# PGTNXEN_pitch_out.net
KiCad netlist of a schematic drawn in EAGLE
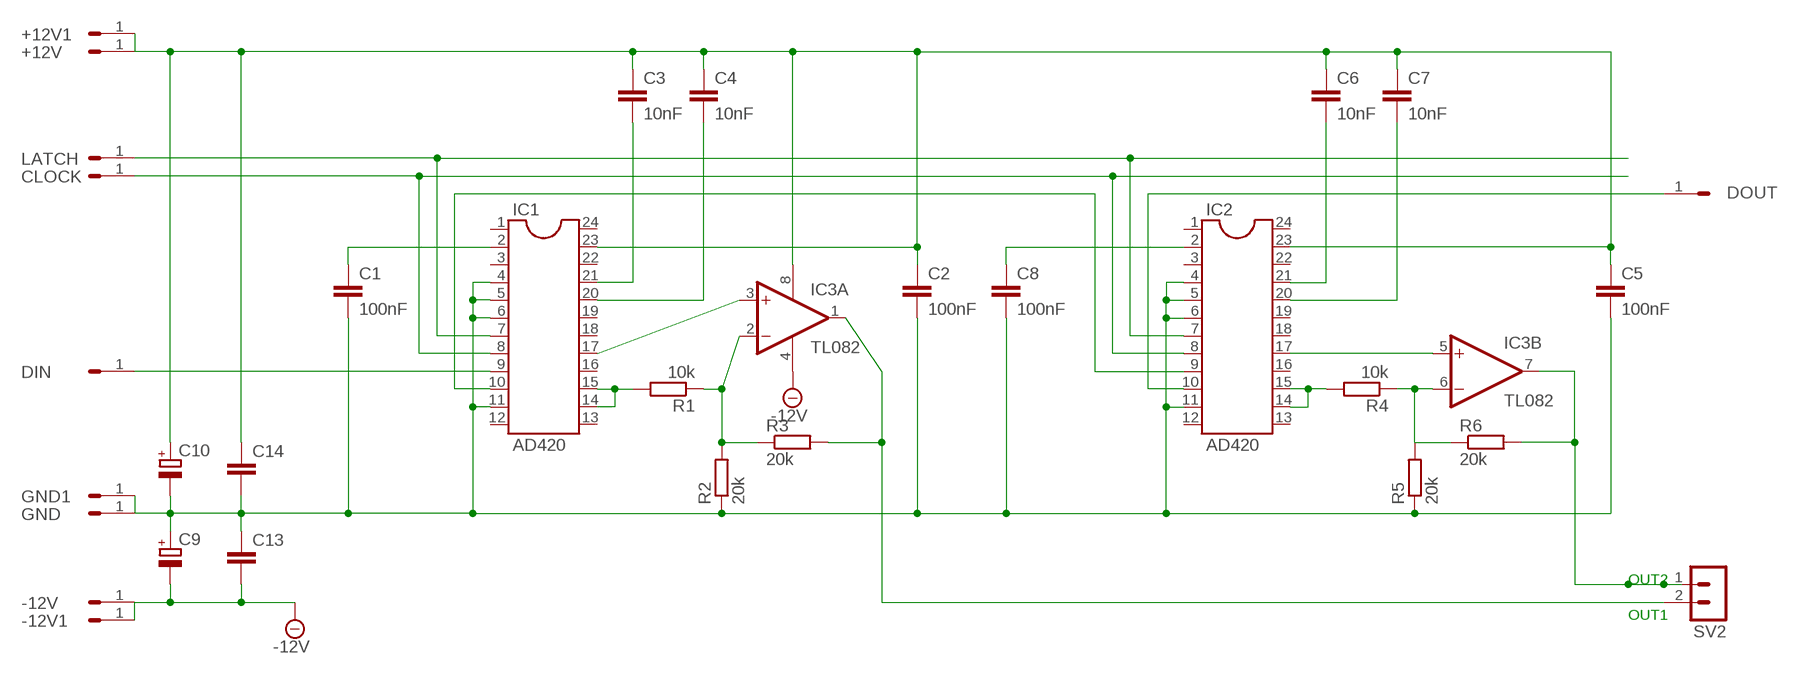
[diagram p0: schematic, sheet 1]

(export (version "E")
  (design (tool "Eeschema 10.0.6"))
  (components
    (comp (ref "+12V")
      (value "HEADER/MALE/01")
      (footprint "eagle-import:HEADER_MALE_01")
      (libsource (lib "eagle-import") (part "HEADER/MALE/01"))
    )
    (comp (ref "+12V1")
      (value "HEADER/MALE/01")
      (footprint "eagle-import:HEADER_MALE_01")
      (libsource (lib "eagle-import") (part "HEADER/MALE/01"))
    )
    (comp (ref "-12V")
      (value "HEADER/MALE/01")
      (footprint "eagle-import:HEADER_MALE_01")
      (libsource (lib "eagle-import") (part "HEADER/MALE/01"))
    )
    (comp (ref "-12V1")
      (value "HEADER/MALE/01")
      (footprint "eagle-import:HEADER_MALE_01")
      (libsource (lib "eagle-import") (part "HEADER/MALE/01"))
    )
    (comp (ref "C1")
      (value "100nF")
      (footprint "eagle-import:CERAMICDISC_5")
      (libsource (lib "eagle-import") (part "CAPACITORCERAMICDISC/5"))
    )
    (comp (ref "C2")
      (value "100nF")
      (footprint "eagle-import:CERAMICDISC_5")
      (libsource (lib "eagle-import") (part "CAPACITORCERAMICDISC/5"))
    )
    (comp (ref "C3")
      (value "10nF")
      (footprint "eagle-import:CERAMICDISC_5")
      (libsource (lib "eagle-import") (part "CAPACITORCERAMICDISC/5"))
    )
    (comp (ref "C4")
      (value "10nF")
      (footprint "eagle-import:CERAMICDISC_5")
      (libsource (lib "eagle-import") (part "CAPACITORCERAMICDISC/5"))
    )
    (comp (ref "C5")
      (value "100nF")
      (footprint "eagle-import:CERAMICDISC_5")
      (libsource (lib "eagle-import") (part "CAPACITORCERAMICDISC/5"))
    )
    (comp (ref "C6")
      (value "10nF")
      (footprint "eagle-import:CERAMICDISC_5")
      (libsource (lib "eagle-import") (part "CAPACITORCERAMICDISC/5"))
    )
    (comp (ref "C7")
      (value "10nF")
      (footprint "eagle-import:CERAMICDISC_5")
      (libsource (lib "eagle-import") (part "CAPACITORCERAMICDISC/5"))
    )
    (comp (ref "C8")
      (value "100nF")
      (footprint "eagle-import:CERAMICDISC_5")
      (libsource (lib "eagle-import") (part "CAPACITORCERAMICDISC/5"))
    )
    (comp (ref "C9")
      (value "CAPACITOR/POLARIZEDE2.5-6")
      (footprint "eagle-import:E2,5-6")
      (libsource (lib "eagle-import") (part "CAPACITOR/POLARIZEDE2.5-6"))
    )
    (comp (ref "C10")
      (value "CAPACITOR/POLARIZEDE2.5-6")
      (footprint "eagle-import:E2,5-6")
      (libsource (lib "eagle-import") (part "CAPACITOR/POLARIZEDE2.5-6"))
    )
    (comp (ref "C13")
      (value "CAPACITORCERAMICDISC/5")
      (footprint "eagle-import:CERAMICDISC_5")
      (libsource (lib "eagle-import") (part "CAPACITORCERAMICDISC/5"))
    )
    (comp (ref "C14")
      (value "CAPACITORCERAMICDISC/5")
      (footprint "eagle-import:CERAMICDISC_5")
      (libsource (lib "eagle-import") (part "CAPACITORCERAMICDISC/5"))
    )
    (comp (ref "CLOCK")
      (value "HEADER/MALE/01")
      (footprint "eagle-import:HEADER_MALE_01")
      (libsource (lib "eagle-import") (part "HEADER/MALE/01"))
    )
    (comp (ref "DIN")
      (value "HEADER/MALE/01")
      (footprint "eagle-import:HEADER_MALE_01")
      (libsource (lib "eagle-import") (part "HEADER/MALE/01"))
    )
    (comp (ref "DOUT")
      (value "HEADER/MALE/01")
      (footprint "eagle-import:HEADER_MALE_01")
      (libsource (lib "eagle-import") (part "HEADER/MALE/01"))
    )
    (comp (ref "GND")
      (value "HEADER/MALE/01")
      (footprint "eagle-import:HEADER_MALE_01")
      (libsource (lib "eagle-import") (part "HEADER/MALE/01"))
    )
    (comp (ref "GND1")
      (value "HEADER/MALE/01")
      (footprint "eagle-import:HEADER_MALE_01")
      (libsource (lib "eagle-import") (part "HEADER/MALE/01"))
    )
    (comp (ref "IC1")
      (value "AD420")
      (footprint "eagle-import:DIL24-3")
      (libsource (lib "eagle-import") (part "DIL24-3"))
    )
    (comp (ref "IC2")
      (value "AD420")
      (footprint "eagle-import:DIL24-3")
      (libsource (lib "eagle-import") (part "DIL24-3"))
    )
    (comp (ref "IC3")
      (value "TL082")
      (footprint "eagle-import:DIL08")
      (libsource (lib "eagle-import") (part "LM358N"))
    )
    (comp (ref "LATCH")
      (value "HEADER/MALE/01")
      (footprint "eagle-import:HEADER_MALE_01")
      (libsource (lib "eagle-import") (part "HEADER/MALE/01"))
    )
    (comp (ref "R1")
      (value "10k")
      (footprint "eagle-import:0204_7")
      (libsource (lib "eagle-import") (part "R-EU_0204/7"))
    )
    (comp (ref "R2")
      (value "20k")
      (footprint "eagle-import:0204_7")
      (libsource (lib "eagle-import") (part "R-EU_0204/7"))
    )
    (comp (ref "R3")
      (value "20k")
      (footprint "eagle-import:RESISTOR_7.5")
      (libsource (lib "eagle-import") (part "RESISTORRESISTOR/UPRIGHT/7.5"))
    )
    (comp (ref "R4")
      (value "10k")
      (footprint "eagle-import:0204_7")
      (libsource (lib "eagle-import") (part "R-EU_0204/7"))
    )
    (comp (ref "R5")
      (value "20k")
      (footprint "eagle-import:0204_7")
      (libsource (lib "eagle-import") (part "R-EU_0204/7"))
    )
    (comp (ref "R6")
      (value "20k")
      (footprint "eagle-import:RESISTOR_7.5")
      (libsource (lib "eagle-import") (part "RESISTORRESISTOR/UPRIGHT/7.5"))
    )
    (comp (ref "SV2")
      (value "HEADER/MALE/02-1")
      (footprint "eagle-import:HEADER_MALE_02-1")
      (libsource (lib "eagle-import") (part "HEADER/MALE/02-1"))
    )
  )
  (nets
    (net (code "1") (name "-12V") (class "Default")
      (node (ref "-12V") (pin "1") (pinfunction "3_1") (pintype "passive"))
      (node (ref "-12V1") (pin "1") (pinfunction "3_1") (pintype "passive"))
      (node (ref "C13") (pin "2") (pinfunction "2_2") (pintype "passive"))
      (node (ref "C9") (pin "-") (pinfunction "-_-") (pintype "passive"))
      (node (ref "IC3") (pin "4") (pinfunction "V-_4") (pintype "power_in"))
    )
    (net (code "2") (name "Net-(+12V-3)") (class "Default")
      (node (ref "+12V") (pin "1") (pinfunction "3_1") (pintype "passive"))
      (node (ref "+12V1") (pin "1") (pinfunction "3_1") (pintype "passive"))
      (node (ref "C10") (pin "+") (pinfunction "+_+") (pintype "passive"))
      (node (ref "C14") (pin "1") (pinfunction "1_1") (pintype "passive"))
      (node (ref "C2") (pin "1") (pinfunction "1_1") (pintype "passive"))
      (node (ref "C3") (pin "1") (pinfunction "1_1") (pintype "passive"))
      (node (ref "C4") (pin "1") (pinfunction "1_1") (pintype "passive"))
      (node (ref "C5") (pin "1") (pinfunction "1_1") (pintype "passive"))
      (node (ref "C6") (pin "1") (pinfunction "1_1") (pintype "passive"))
      (node (ref "C7") (pin "1") (pinfunction "1_1") (pintype "passive"))
      (node (ref "IC1") (pin "23") (pinfunction "23_23") (pintype "passive"))
      (node (ref "IC2") (pin "23") (pinfunction "23_23") (pintype "passive"))
      (node (ref "IC3") (pin "8") (pinfunction "V+_8") (pintype "power_in"))
    )
    (net (code "3") (name "Net-(C1-Pad1)") (class "Default")
      (node (ref "C1") (pin "1") (pinfunction "1_1") (pintype "passive"))
      (node (ref "IC1") (pin "2") (pinfunction "2_2") (pintype "passive"))
    )
    (net (code "4") (name "Net-(C3-Pad2)") (class "Default")
      (node (ref "C3") (pin "2") (pinfunction "2_2") (pintype "passive"))
      (node (ref "IC1") (pin "21") (pinfunction "21_21") (pintype "passive"))
    )
    (net (code "5") (name "Net-(C4-Pad2)") (class "Default")
      (node (ref "C4") (pin "2") (pinfunction "2_2") (pintype "passive"))
      (node (ref "IC1") (pin "20") (pinfunction "20_20") (pintype "passive"))
    )
    (net (code "6") (name "Net-(C6-Pad2)") (class "Default")
      (node (ref "C6") (pin "2") (pinfunction "2_2") (pintype "passive"))
      (node (ref "IC2") (pin "21") (pinfunction "21_21") (pintype "passive"))
    )
    (net (code "7") (name "Net-(C7-Pad2)") (class "Default")
      (node (ref "C7") (pin "2") (pinfunction "2_2") (pintype "passive"))
      (node (ref "IC2") (pin "20") (pinfunction "20_20") (pintype "passive"))
    )
    (net (code "8") (name "Net-(C8-Pad1)") (class "Default")
      (node (ref "C8") (pin "1") (pinfunction "1_1") (pintype "passive"))
      (node (ref "IC2") (pin "2") (pinfunction "2_2") (pintype "passive"))
    )
    (net (code "9") (name "Net-(CLOCK-3)") (class "Default")
      (node (ref "CLOCK") (pin "1") (pinfunction "3_1") (pintype "passive"))
      (node (ref "IC1") (pin "8") (pinfunction "8_8") (pintype "passive"))
      (node (ref "IC2") (pin "8") (pinfunction "8_8") (pintype "passive"))
    )
    (net (code "10") (name "Net-(DIN-3)") (class "Default")
      (node (ref "DIN") (pin "1") (pinfunction "3_1") (pintype "passive"))
      (node (ref "IC1") (pin "9") (pinfunction "9_9") (pintype "passive"))
    )
    (net (code "11") (name "Net-(DOUT-3)") (class "Default")
      (node (ref "DOUT") (pin "1") (pinfunction "3_1") (pintype "passive"))
      (node (ref "IC2") (pin "10") (pinfunction "10_10") (pintype "passive"))
    )
    (net (code "12") (name "Net-(GND-3)") (class "Default")
      (node (ref "C1") (pin "2") (pinfunction "2_2") (pintype "passive"))
      (node (ref "C10") (pin "-") (pinfunction "-_-") (pintype "passive"))
      (node (ref "C13") (pin "1") (pinfunction "1_1") (pintype "passive"))
      (node (ref "C14") (pin "2") (pinfunction "2_2") (pintype "passive"))
      (node (ref "C2") (pin "2") (pinfunction "2_2") (pintype "passive"))
      (node (ref "C5") (pin "2") (pinfunction "2_2") (pintype "passive"))
      (node (ref "C8") (pin "2") (pinfunction "2_2") (pintype "passive"))
      (node (ref "C9") (pin "+") (pinfunction "+_+") (pintype "passive"))
      (node (ref "GND") (pin "1") (pinfunction "3_1") (pintype "passive"))
      (node (ref "GND1") (pin "1") (pinfunction "3_1") (pintype "passive"))
      (node (ref "IC1") (pin "11") (pinfunction "11_11") (pintype "passive"))
      (node (ref "IC1") (pin "4") (pinfunction "4_4") (pintype "passive"))
      (node (ref "IC1") (pin "5") (pinfunction "5_5") (pintype "passive"))
      (node (ref "IC1") (pin "6") (pinfunction "6_6") (pintype "passive"))
      (node (ref "IC2") (pin "11") (pinfunction "11_11") (pintype "passive"))
      (node (ref "IC2") (pin "4") (pinfunction "4_4") (pintype "passive"))
      (node (ref "IC2") (pin "5") (pinfunction "5_5") (pintype "passive"))
      (node (ref "IC2") (pin "6") (pinfunction "6_6") (pintype "passive"))
      (node (ref "R2") (pin "1") (pinfunction "1_1") (pintype "passive"))
      (node (ref "R5") (pin "1") (pinfunction "1_1") (pintype "passive"))
    )
    (net (code "13") (name "Net-(IC1-Pad10)") (class "Default")
      (node (ref "IC1") (pin "10") (pinfunction "10_10") (pintype "passive"))
      (node (ref "IC2") (pin "9") (pinfunction "9_9") (pintype "passive"))
    )
    (net (code "14") (name "Net-(IC1-Pad14)") (class "Default")
      (node (ref "IC1") (pin "14") (pinfunction "14_14") (pintype "passive"))
      (node (ref "IC1") (pin "15") (pinfunction "15_15") (pintype "passive"))
      (node (ref "R1") (pin "2") (pinfunction "2_2") (pintype "passive"))
    )
    (net (code "15") (name "Net-(IC2-Pad14)") (class "Default")
      (node (ref "IC2") (pin "14") (pinfunction "14_14") (pintype "passive"))
      (node (ref "IC2") (pin "15") (pinfunction "15_15") (pintype "passive"))
      (node (ref "R4") (pin "2") (pinfunction "2_2") (pintype "passive"))
    )
    (net (code "16") (name "Net-(IC3A-+IN)") (class "Default")
      (node (ref "IC1") (pin "17") (pinfunction "17_17") (pintype "passive"))
      (node (ref "IC3") (pin "3") (pinfunction "+IN_3") (pintype "input"))
    )
    (net (code "17") (name "Net-(IC3A--IN)") (class "Default")
      (node (ref "IC3") (pin "2") (pinfunction "-IN_2") (pintype "input"))
      (node (ref "R1") (pin "1") (pinfunction "1_1") (pintype "passive"))
      (node (ref "R2") (pin "2") (pinfunction "2_2") (pintype "passive"))
      (node (ref "R3") (pin "1") (pinfunction "1_1") (pintype "passive"))
    )
    (net (code "18") (name "Net-(IC3A-OUT)") (class "Default")
      (node (ref "IC3") (pin "1") (pinfunction "OUT_1") (pintype "output"))
      (node (ref "R3") (pin "2") (pinfunction "2_2") (pintype "passive"))
      (node (ref "SV2") (pin "2") (pinfunction "3_2") (pintype "passive"))
    )
    (net (code "19") (name "Net-(IC3B-+IN)") (class "Default")
      (node (ref "IC2") (pin "17") (pinfunction "17_17") (pintype "passive"))
      (node (ref "IC3") (pin "5") (pinfunction "+IN_5") (pintype "input"))
    )
    (net (code "20") (name "Net-(IC3B--IN)") (class "Default")
      (node (ref "IC3") (pin "6") (pinfunction "-IN_6") (pintype "input"))
      (node (ref "R4") (pin "1") (pinfunction "1_1") (pintype "passive"))
      (node (ref "R5") (pin "2") (pinfunction "2_2") (pintype "passive"))
      (node (ref "R6") (pin "1") (pinfunction "1_1") (pintype "passive"))
    )
    (net (code "21") (name "Net-(IC3B-OUT)") (class "Default")
      (node (ref "IC3") (pin "7") (pinfunction "OUT_7") (pintype "output"))
      (node (ref "R6") (pin "2") (pinfunction "2_2") (pintype "passive"))
      (node (ref "SV2") (pin "1") (pinfunction "2_1") (pintype "passive"))
    )
    (net (code "22") (name "Net-(LATCH-3)") (class "Default")
      (node (ref "IC1") (pin "7") (pinfunction "7_7") (pintype "passive"))
      (node (ref "IC2") (pin "7") (pinfunction "7_7") (pintype "passive"))
      (node (ref "LATCH") (pin "1") (pinfunction "3_1") (pintype "passive"))
    )
    (net (code "23") (name "unconnected-(IC1-Pad1)") (class "Default")
      (node (ref "IC1") (pin "1") (pinfunction "1_1") (pintype "passive"))
    )
    (net (code "24") (name "unconnected-(IC1-Pad3)") (class "Default")
      (node (ref "IC1") (pin "3") (pinfunction "3_3") (pintype "passive"))
    )
    (net (code "25") (name "unconnected-(IC1-Pad12)") (class "Default")
      (node (ref "IC1") (pin "12") (pinfunction "12_12") (pintype "passive"))
    )
    (net (code "26") (name "unconnected-(IC1-Pad13)") (class "Default")
      (node (ref "IC1") (pin "13") (pinfunction "13_13") (pintype "passive"))
    )
    (net (code "27") (name "unconnected-(IC1-Pad16)") (class "Default")
      (node (ref "IC1") (pin "16") (pinfunction "16_16") (pintype "passive"))
    )
    (net (code "28") (name "unconnected-(IC1-Pad18)") (class "Default")
      (node (ref "IC1") (pin "18") (pinfunction "18_18") (pintype "passive"))
    )
    (net (code "29") (name "unconnected-(IC1-Pad19)") (class "Default")
      (node (ref "IC1") (pin "19") (pinfunction "19_19") (pintype "passive"))
    )
    (net (code "30") (name "unconnected-(IC1-Pad22)") (class "Default")
      (node (ref "IC1") (pin "22") (pinfunction "22_22") (pintype "passive"))
    )
    (net (code "31") (name "unconnected-(IC1-Pad24)") (class "Default")
      (node (ref "IC1") (pin "24") (pinfunction "24_24") (pintype "passive"))
    )
    (net (code "32") (name "unconnected-(IC2-Pad1)") (class "Default")
      (node (ref "IC2") (pin "1") (pinfunction "1_1") (pintype "passive"))
    )
    (net (code "33") (name "unconnected-(IC2-Pad3)") (class "Default")
      (node (ref "IC2") (pin "3") (pinfunction "3_3") (pintype "passive"))
    )
    (net (code "34") (name "unconnected-(IC2-Pad12)") (class "Default")
      (node (ref "IC2") (pin "12") (pinfunction "12_12") (pintype "passive"))
    )
    (net (code "35") (name "unconnected-(IC2-Pad13)") (class "Default")
      (node (ref "IC2") (pin "13") (pinfunction "13_13") (pintype "passive"))
    )
    (net (code "36") (name "unconnected-(IC2-Pad16)") (class "Default")
      (node (ref "IC2") (pin "16") (pinfunction "16_16") (pintype "passive"))
    )
    (net (code "37") (name "unconnected-(IC2-Pad18)") (class "Default")
      (node (ref "IC2") (pin "18") (pinfunction "18_18") (pintype "passive"))
    )
    (net (code "38") (name "unconnected-(IC2-Pad19)") (class "Default")
      (node (ref "IC2") (pin "19") (pinfunction "19_19") (pintype "passive"))
    )
    (net (code "39") (name "unconnected-(IC2-Pad22)") (class "Default")
      (node (ref "IC2") (pin "22") (pinfunction "22_22") (pintype "passive"))
    )
    (net (code "40") (name "unconnected-(IC2-Pad24)") (class "Default")
      (node (ref "IC2") (pin "24") (pinfunction "24_24") (pintype "passive"))
    )
  )
)
